# Pendu_LED.net
KiCad netlist of a schematic drawn in EasyEDA
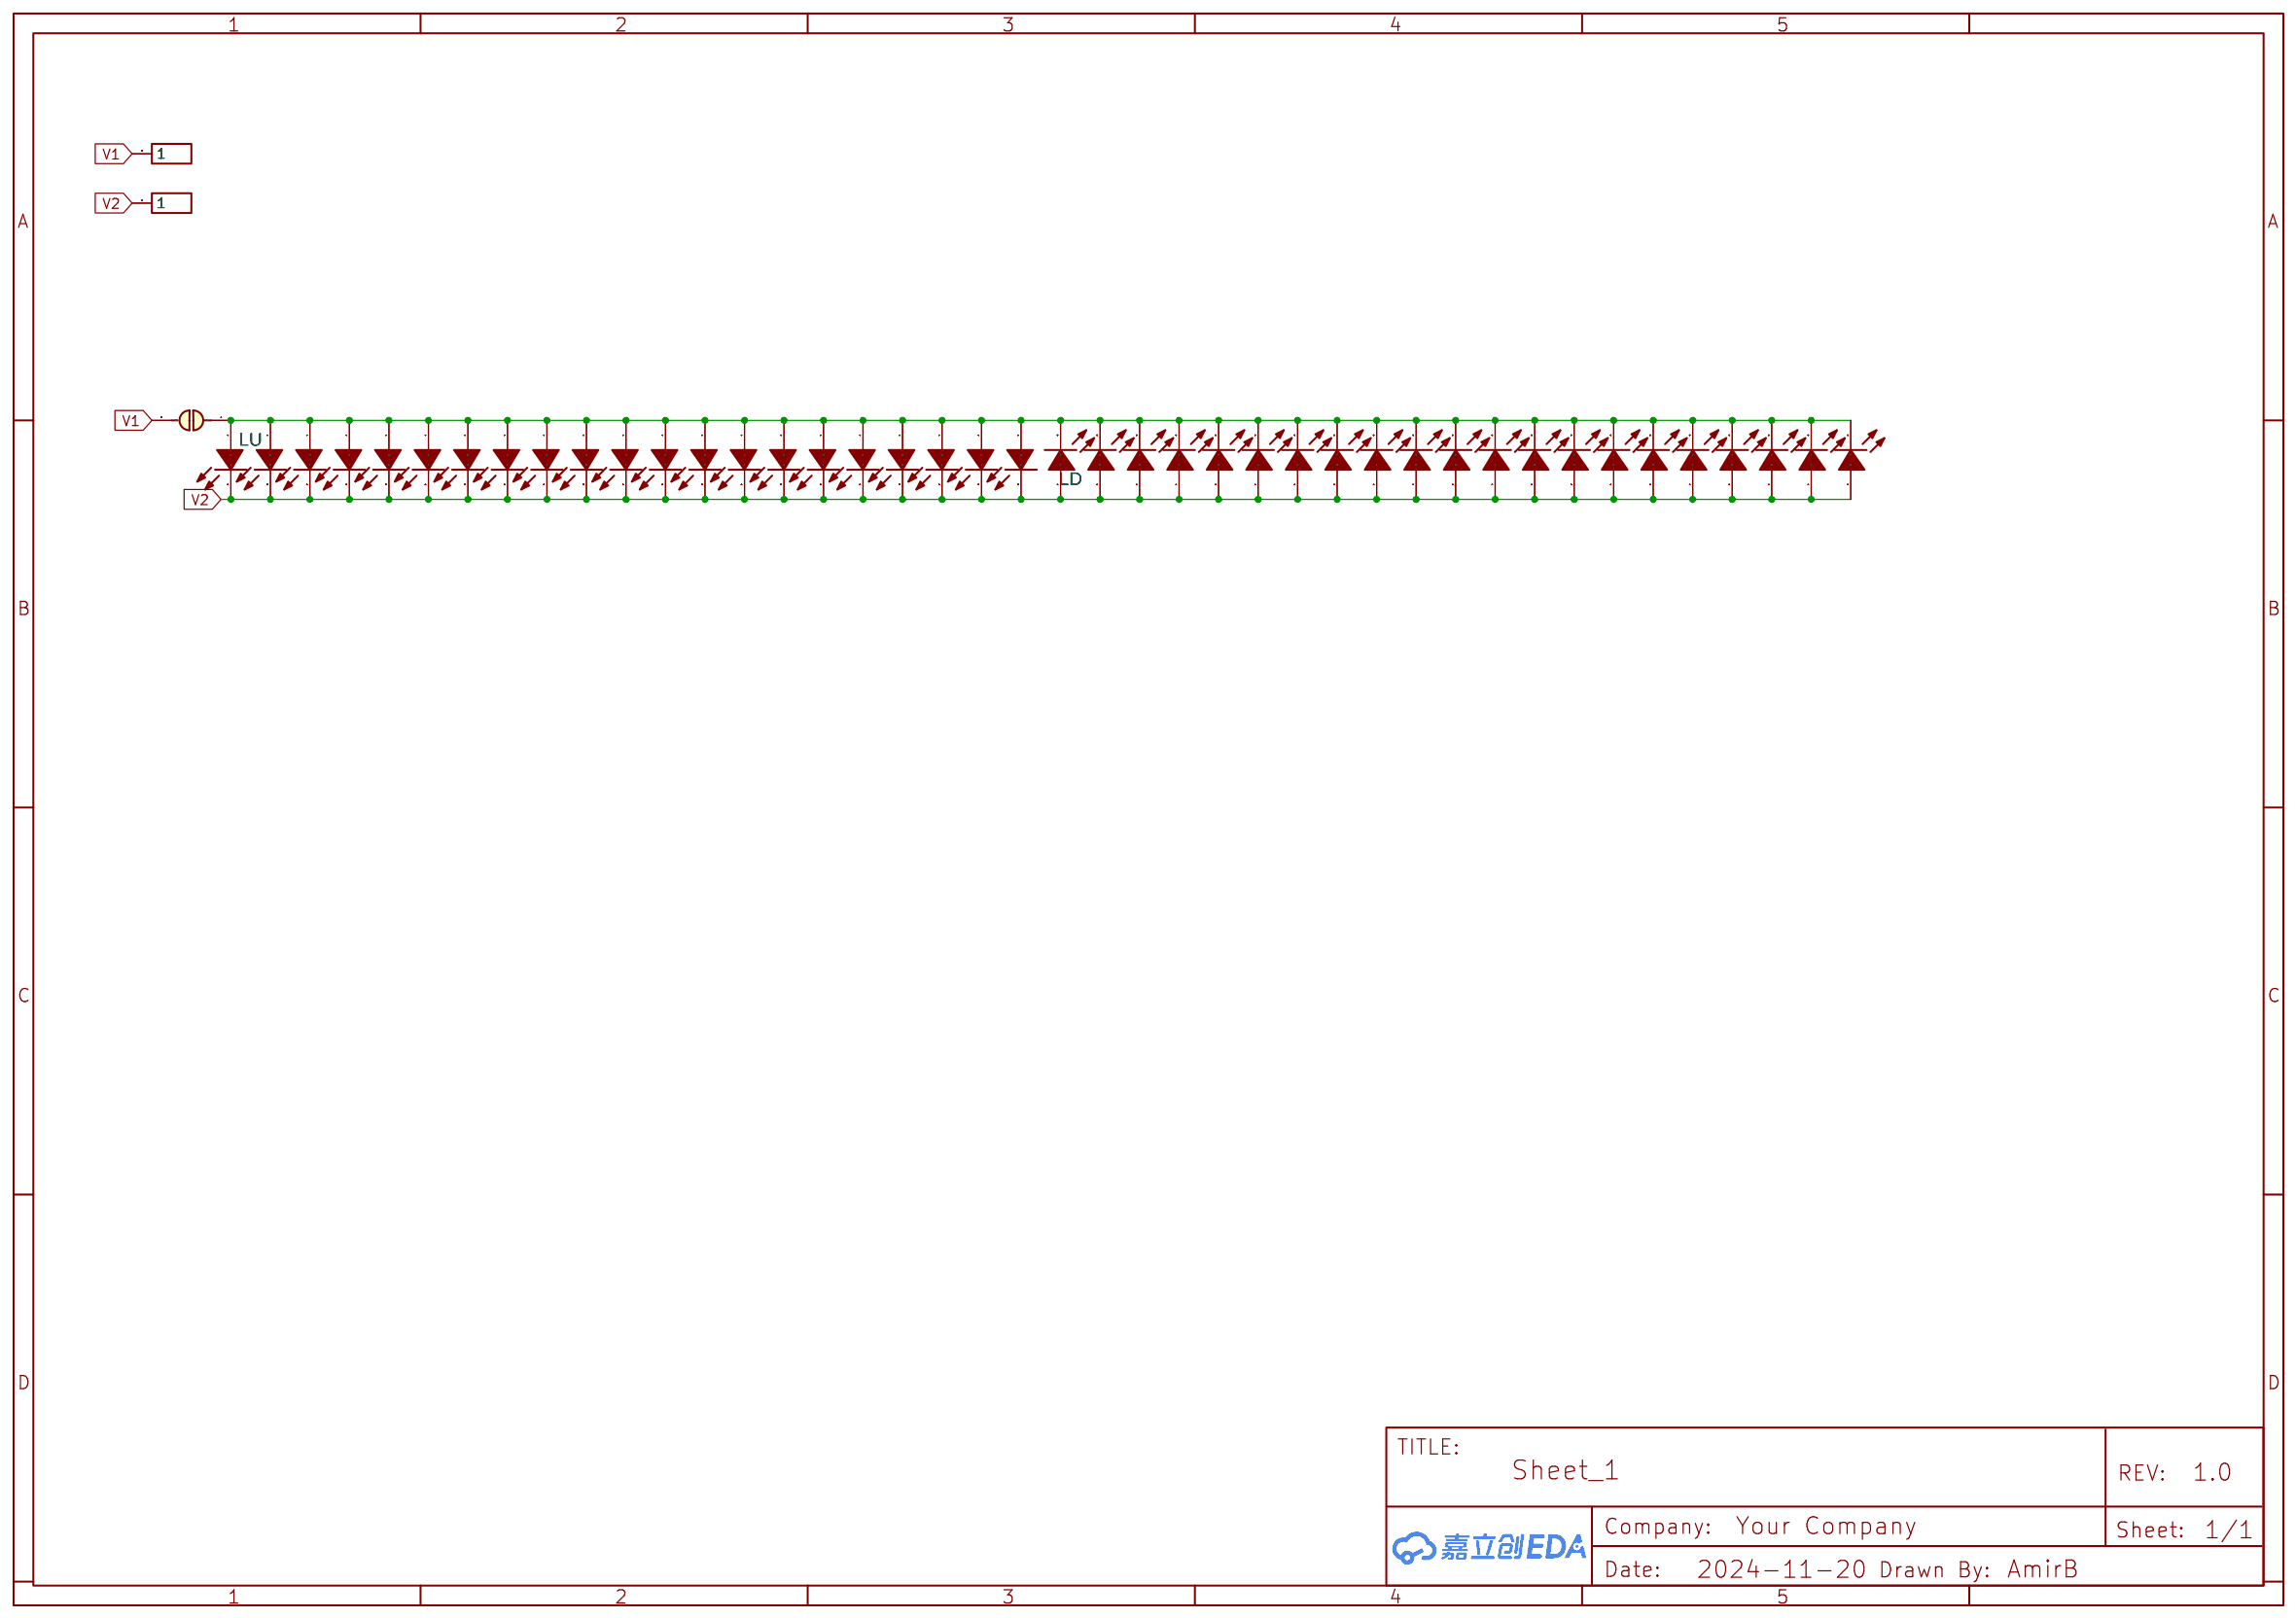
[diagram p0: schematic sheet]

(export (version "E")
  (design (tool "Eeschema 10.0.6"))
  (components
    (comp (ref "J1")
      (value "HDR-M-2.54_1x1")
      (fields (field (name "BOM_Supplier Part") "C81276"))
      (libsource (lib "") (part "HDR-M-2.54_1x1"))
    )
    (comp (ref "J2")
      (value "HDR-M-2.54_1x1")
      (fields (field (name "BOM_Supplier Part") "C81276"))
      (libsource (lib "") (part "HDR-M-2.54_1x1"))
    )
    (comp (ref "JU1") (value "JUMPER-RESET") (libsource (lib "") (part "JUMPER-SMT_2")))
    (comp (ref "LD")
      (value "FC-2012HRK-620D")
      (fields (field (name "Manufacturer Part") "NCD0805R1") (field (name "Manufacturer") "国星光电"))
      (libsource (lib "") (part "FC-2012HRK-620D"))
    )
    (comp (ref "LD1")
      (value "FC-2012HRK-620D")
      (fields (field (name "Manufacturer Part") "NCD0805R1") (field (name "Manufacturer") "国星光电"))
      (libsource (lib "") (part "FC-2012HRK-620D"))
    )
    (comp (ref "LD2")
      (value "FC-2012HRK-620D")
      (fields (field (name "Manufacturer Part") "NCD0805R1") (field (name "Manufacturer") "国星光电"))
      (libsource (lib "") (part "FC-2012HRK-620D"))
    )
    (comp (ref "LD3")
      (value "FC-2012HRK-620D")
      (fields (field (name "Manufacturer Part") "NCD0805R1") (field (name "Manufacturer") "国星光电"))
      (libsource (lib "") (part "FC-2012HRK-620D"))
    )
    (comp (ref "LD4")
      (value "FC-2012HRK-620D")
      (fields (field (name "Manufacturer Part") "NCD0805R1") (field (name "Manufacturer") "国星光电"))
      (libsource (lib "") (part "FC-2012HRK-620D"))
    )
    (comp (ref "LD5")
      (value "FC-2012HRK-620D")
      (fields (field (name "Manufacturer Part") "NCD0805R1") (field (name "Manufacturer") "国星光电"))
      (libsource (lib "") (part "FC-2012HRK-620D"))
    )
    (comp (ref "LD6")
      (value "FC-2012HRK-620D")
      (fields (field (name "Manufacturer Part") "NCD0805R1") (field (name "Manufacturer") "国星光电"))
      (libsource (lib "") (part "FC-2012HRK-620D"))
    )
    (comp (ref "LD7")
      (value "FC-2012HRK-620D")
      (fields (field (name "Manufacturer Part") "NCD0805R1") (field (name "Manufacturer") "国星光电"))
      (libsource (lib "") (part "FC-2012HRK-620D"))
    )
    (comp (ref "LD8")
      (value "FC-2012HRK-620D")
      (fields (field (name "Manufacturer Part") "NCD0805R1") (field (name "Manufacturer") "国星光电"))
      (libsource (lib "") (part "FC-2012HRK-620D"))
    )
    (comp (ref "LD9")
      (value "FC-2012HRK-620D")
      (fields (field (name "Manufacturer Part") "NCD0805R1") (field (name "Manufacturer") "国星光电"))
      (libsource (lib "") (part "FC-2012HRK-620D"))
    )
    (comp (ref "LD10")
      (value "FC-2012HRK-620D")
      (fields (field (name "Manufacturer Part") "NCD0805R1") (field (name "Manufacturer") "国星光电"))
      (libsource (lib "") (part "FC-2012HRK-620D"))
    )
    (comp (ref "LD11")
      (value "FC-2012HRK-620D")
      (fields (field (name "Manufacturer Part") "NCD0805R1") (field (name "Manufacturer") "国星光电"))
      (libsource (lib "") (part "FC-2012HRK-620D"))
    )
    (comp (ref "LD12")
      (value "FC-2012HRK-620D")
      (fields (field (name "Manufacturer Part") "NCD0805R1") (field (name "Manufacturer") "国星光电"))
      (libsource (lib "") (part "FC-2012HRK-620D"))
    )
    (comp (ref "LD13")
      (value "FC-2012HRK-620D")
      (fields (field (name "Manufacturer Part") "NCD0805R1") (field (name "Manufacturer") "国星光电"))
      (libsource (lib "") (part "FC-2012HRK-620D"))
    )
    (comp (ref "LD14")
      (value "FC-2012HRK-620D")
      (fields (field (name "Manufacturer Part") "NCD0805R1") (field (name "Manufacturer") "国星光电"))
      (libsource (lib "") (part "FC-2012HRK-620D"))
    )
    (comp (ref "LD15")
      (value "FC-2012HRK-620D")
      (fields (field (name "Manufacturer Part") "NCD0805R1") (field (name "Manufacturer") "国星光电"))
      (libsource (lib "") (part "FC-2012HRK-620D"))
    )
    (comp (ref "LD16")
      (value "FC-2012HRK-620D")
      (fields (field (name "Manufacturer Part") "NCD0805R1") (field (name "Manufacturer") "国星光电"))
      (libsource (lib "") (part "FC-2012HRK-620D"))
    )
    (comp (ref "LD17")
      (value "FC-2012HRK-620D")
      (fields (field (name "Manufacturer Part") "NCD0805R1") (field (name "Manufacturer") "国星光电"))
      (libsource (lib "") (part "FC-2012HRK-620D"))
    )
    (comp (ref "LD18")
      (value "FC-2012HRK-620D")
      (fields (field (name "Manufacturer Part") "NCD0805R1") (field (name "Manufacturer") "国星光电"))
      (libsource (lib "") (part "FC-2012HRK-620D"))
    )
    (comp (ref "LD19")
      (value "FC-2012HRK-620D")
      (fields (field (name "Manufacturer Part") "NCD0805R1") (field (name "Manufacturer") "国星光电"))
      (libsource (lib "") (part "FC-2012HRK-620D"))
    )
    (comp (ref "LD20")
      (value "FC-2012HRK-620D")
      (fields (field (name "Manufacturer Part") "NCD0805R1") (field (name "Manufacturer") "国星光电"))
      (libsource (lib "") (part "FC-2012HRK-620D"))
    )
    (comp (ref "LU")
      (value "FC-2012HRK-620D")
      (fields (field (name "Manufacturer Part") "NCD0805R1") (field (name "Manufacturer") "国星光电"))
      (libsource (lib "") (part "FC-2012HRK-620D_1"))
    )
    (comp (ref "LU1")
      (value "FC-2012HRK-620D")
      (fields (field (name "Manufacturer Part") "NCD0805R1") (field (name "Manufacturer") "国星光电"))
      (libsource (lib "") (part "FC-2012HRK-620D_1"))
    )
    (comp (ref "LU2")
      (value "FC-2012HRK-620D")
      (fields (field (name "Manufacturer Part") "NCD0805R1") (field (name "Manufacturer") "国星光电"))
      (libsource (lib "") (part "FC-2012HRK-620D_1"))
    )
    (comp (ref "LU3")
      (value "FC-2012HRK-620D")
      (fields (field (name "Manufacturer Part") "NCD0805R1") (field (name "Manufacturer") "国星光电"))
      (libsource (lib "") (part "FC-2012HRK-620D_1"))
    )
    (comp (ref "LU4")
      (value "FC-2012HRK-620D")
      (fields (field (name "Manufacturer Part") "NCD0805R1") (field (name "Manufacturer") "国星光电"))
      (libsource (lib "") (part "FC-2012HRK-620D_1"))
    )
    (comp (ref "LU5")
      (value "FC-2012HRK-620D")
      (fields (field (name "Manufacturer Part") "NCD0805R1") (field (name "Manufacturer") "国星光电"))
      (libsource (lib "") (part "FC-2012HRK-620D_1"))
    )
    (comp (ref "LU6")
      (value "FC-2012HRK-620D")
      (fields (field (name "Manufacturer Part") "NCD0805R1") (field (name "Manufacturer") "国星光电"))
      (libsource (lib "") (part "FC-2012HRK-620D_1"))
    )
    (comp (ref "LU7")
      (value "FC-2012HRK-620D")
      (fields (field (name "Manufacturer Part") "NCD0805R1") (field (name "Manufacturer") "国星光电"))
      (libsource (lib "") (part "FC-2012HRK-620D_1"))
    )
    (comp (ref "LU8")
      (value "FC-2012HRK-620D")
      (fields (field (name "Manufacturer Part") "NCD0805R1") (field (name "Manufacturer") "国星光电"))
      (libsource (lib "") (part "FC-2012HRK-620D_1"))
    )
    (comp (ref "LU9")
      (value "FC-2012HRK-620D")
      (fields (field (name "Manufacturer Part") "NCD0805R1") (field (name "Manufacturer") "国星光电"))
      (libsource (lib "") (part "FC-2012HRK-620D_1"))
    )
    (comp (ref "LU10")
      (value "FC-2012HRK-620D")
      (fields (field (name "Manufacturer Part") "NCD0805R1") (field (name "Manufacturer") "国星光电"))
      (libsource (lib "") (part "FC-2012HRK-620D_1"))
    )
    (comp (ref "LU11")
      (value "FC-2012HRK-620D")
      (fields (field (name "Manufacturer Part") "NCD0805R1") (field (name "Manufacturer") "国星光电"))
      (libsource (lib "") (part "FC-2012HRK-620D_1"))
    )
    (comp (ref "LU12")
      (value "FC-2012HRK-620D")
      (fields (field (name "Manufacturer Part") "NCD0805R1") (field (name "Manufacturer") "国星光电"))
      (libsource (lib "") (part "FC-2012HRK-620D_1"))
    )
    (comp (ref "LU13")
      (value "FC-2012HRK-620D")
      (fields (field (name "Manufacturer Part") "NCD0805R1") (field (name "Manufacturer") "国星光电"))
      (libsource (lib "") (part "FC-2012HRK-620D_1"))
    )
    (comp (ref "LU14")
      (value "FC-2012HRK-620D")
      (fields (field (name "Manufacturer Part") "NCD0805R1") (field (name "Manufacturer") "国星光电"))
      (libsource (lib "") (part "FC-2012HRK-620D_1"))
    )
    (comp (ref "LU15")
      (value "FC-2012HRK-620D")
      (fields (field (name "Manufacturer Part") "NCD0805R1") (field (name "Manufacturer") "国星光电"))
      (libsource (lib "") (part "FC-2012HRK-620D_1"))
    )
    (comp (ref "LU16")
      (value "FC-2012HRK-620D")
      (fields (field (name "Manufacturer Part") "NCD0805R1") (field (name "Manufacturer") "国星光电"))
      (libsource (lib "") (part "FC-2012HRK-620D_1"))
    )
    (comp (ref "LU17")
      (value "FC-2012HRK-620D")
      (fields (field (name "Manufacturer Part") "NCD0805R1") (field (name "Manufacturer") "国星光电"))
      (libsource (lib "") (part "FC-2012HRK-620D_1"))
    )
    (comp (ref "LU18")
      (value "FC-2012HRK-620D")
      (fields (field (name "Manufacturer Part") "NCD0805R1") (field (name "Manufacturer") "国星光电"))
      (libsource (lib "") (part "FC-2012HRK-620D_1"))
    )
    (comp (ref "LU19")
      (value "FC-2012HRK-620D")
      (fields (field (name "Manufacturer Part") "NCD0805R1") (field (name "Manufacturer") "国星光电"))
      (libsource (lib "") (part "FC-2012HRK-620D_1"))
    )
    (comp (ref "LU20")
      (value "FC-2012HRK-620D")
      (fields (field (name "Manufacturer Part") "NCD0805R1") (field (name "Manufacturer") "国星光电"))
      (libsource (lib "") (part "FC-2012HRK-620D_1"))
    )
  )
  (nets
    (net (code "1") (name "Net-(LD--)") (class "Default")
      (node (ref "JU1") (pin "1") (pinfunction "1_1") (pintype "bidirectional"))
      (node (ref "LD") (pin "2") (pinfunction "-_2") (pintype "unspecified"))
      (node (ref "LD1") (pin "2") (pinfunction "-_2") (pintype "unspecified"))
      (node (ref "LD10") (pin "2") (pinfunction "-_2") (pintype "unspecified"))
      (node (ref "LD11") (pin "2") (pinfunction "-_2") (pintype "unspecified"))
      (node (ref "LD12") (pin "2") (pinfunction "-_2") (pintype "unspecified"))
      (node (ref "LD13") (pin "2") (pinfunction "-_2") (pintype "unspecified"))
      (node (ref "LD14") (pin "2") (pinfunction "-_2") (pintype "unspecified"))
      (node (ref "LD15") (pin "2") (pinfunction "-_2") (pintype "unspecified"))
      (node (ref "LD16") (pin "2") (pinfunction "-_2") (pintype "unspecified"))
      (node (ref "LD17") (pin "2") (pinfunction "-_2") (pintype "unspecified"))
      (node (ref "LD18") (pin "2") (pinfunction "-_2") (pintype "unspecified"))
      (node (ref "LD19") (pin "2") (pinfunction "-_2") (pintype "unspecified"))
      (node (ref "LD2") (pin "2") (pinfunction "-_2") (pintype "unspecified"))
      (node (ref "LD20") (pin "2") (pinfunction "-_2") (pintype "unspecified"))
      (node (ref "LD3") (pin "2") (pinfunction "-_2") (pintype "unspecified"))
      (node (ref "LD4") (pin "2") (pinfunction "-_2") (pintype "unspecified"))
      (node (ref "LD5") (pin "2") (pinfunction "-_2") (pintype "unspecified"))
      (node (ref "LD6") (pin "2") (pinfunction "-_2") (pintype "unspecified"))
      (node (ref "LD7") (pin "2") (pinfunction "-_2") (pintype "unspecified"))
      (node (ref "LD8") (pin "2") (pinfunction "-_2") (pintype "unspecified"))
      (node (ref "LD9") (pin "2") (pinfunction "-_2") (pintype "unspecified"))
      (node (ref "LU") (pin "1") (pinfunction "+_1") (pintype "unspecified"))
      (node (ref "LU1") (pin "1") (pinfunction "+_1") (pintype "unspecified"))
      (node (ref "LU10") (pin "1") (pinfunction "+_1") (pintype "unspecified"))
      (node (ref "LU11") (pin "1") (pinfunction "+_1") (pintype "unspecified"))
      (node (ref "LU12") (pin "1") (pinfunction "+_1") (pintype "unspecified"))
      (node (ref "LU13") (pin "1") (pinfunction "+_1") (pintype "unspecified"))
      (node (ref "LU14") (pin "1") (pinfunction "+_1") (pintype "unspecified"))
      (node (ref "LU15") (pin "1") (pinfunction "+_1") (pintype "unspecified"))
      (node (ref "LU16") (pin "1") (pinfunction "+_1") (pintype "unspecified"))
      (node (ref "LU17") (pin "1") (pinfunction "+_1") (pintype "unspecified"))
      (node (ref "LU18") (pin "1") (pinfunction "+_1") (pintype "unspecified"))
      (node (ref "LU19") (pin "1") (pinfunction "+_1") (pintype "unspecified"))
      (node (ref "LU2") (pin "1") (pinfunction "+_1") (pintype "unspecified"))
      (node (ref "LU20") (pin "1") (pinfunction "+_1") (pintype "unspecified"))
      (node (ref "LU3") (pin "1") (pinfunction "+_1") (pintype "unspecified"))
      (node (ref "LU4") (pin "1") (pinfunction "+_1") (pintype "unspecified"))
      (node (ref "LU5") (pin "1") (pinfunction "+_1") (pintype "unspecified"))
      (node (ref "LU6") (pin "1") (pinfunction "+_1") (pintype "unspecified"))
      (node (ref "LU7") (pin "1") (pinfunction "+_1") (pintype "unspecified"))
      (node (ref "LU8") (pin "1") (pinfunction "+_1") (pintype "unspecified"))
      (node (ref "LU9") (pin "1") (pinfunction "+_1") (pintype "unspecified"))
    )
    (net (code "2") (name "V1") (class "Default")
      (node (ref "J1") (pin "1") (pinfunction "1_1") (pintype "input"))
      (node (ref "JU1") (pin "2") (pinfunction "2_2") (pintype "bidirectional"))
    )
    (net (code "3") (name "V2") (class "Default")
      (node (ref "J2") (pin "1") (pinfunction "1_1") (pintype "input"))
      (node (ref "LD") (pin "1") (pinfunction "+_1") (pintype "unspecified"))
      (node (ref "LD1") (pin "1") (pinfunction "+_1") (pintype "unspecified"))
      (node (ref "LD10") (pin "1") (pinfunction "+_1") (pintype "unspecified"))
      (node (ref "LD11") (pin "1") (pinfunction "+_1") (pintype "unspecified"))
      (node (ref "LD12") (pin "1") (pinfunction "+_1") (pintype "unspecified"))
      (node (ref "LD13") (pin "1") (pinfunction "+_1") (pintype "unspecified"))
      (node (ref "LD14") (pin "1") (pinfunction "+_1") (pintype "unspecified"))
      (node (ref "LD15") (pin "1") (pinfunction "+_1") (pintype "unspecified"))
      (node (ref "LD16") (pin "1") (pinfunction "+_1") (pintype "unspecified"))
      (node (ref "LD17") (pin "1") (pinfunction "+_1") (pintype "unspecified"))
      (node (ref "LD18") (pin "1") (pinfunction "+_1") (pintype "unspecified"))
      (node (ref "LD19") (pin "1") (pinfunction "+_1") (pintype "unspecified"))
      (node (ref "LD2") (pin "1") (pinfunction "+_1") (pintype "unspecified"))
      (node (ref "LD20") (pin "1") (pinfunction "+_1") (pintype "unspecified"))
      (node (ref "LD3") (pin "1") (pinfunction "+_1") (pintype "unspecified"))
      (node (ref "LD4") (pin "1") (pinfunction "+_1") (pintype "unspecified"))
      (node (ref "LD5") (pin "1") (pinfunction "+_1") (pintype "unspecified"))
      (node (ref "LD6") (pin "1") (pinfunction "+_1") (pintype "unspecified"))
      (node (ref "LD7") (pin "1") (pinfunction "+_1") (pintype "unspecified"))
      (node (ref "LD8") (pin "1") (pinfunction "+_1") (pintype "unspecified"))
      (node (ref "LD9") (pin "1") (pinfunction "+_1") (pintype "unspecified"))
      (node (ref "LU") (pin "2") (pinfunction "-_2") (pintype "unspecified"))
      (node (ref "LU1") (pin "2") (pinfunction "-_2") (pintype "unspecified"))
      (node (ref "LU10") (pin "2") (pinfunction "-_2") (pintype "unspecified"))
      (node (ref "LU11") (pin "2") (pinfunction "-_2") (pintype "unspecified"))
      (node (ref "LU12") (pin "2") (pinfunction "-_2") (pintype "unspecified"))
      (node (ref "LU13") (pin "2") (pinfunction "-_2") (pintype "unspecified"))
      (node (ref "LU14") (pin "2") (pinfunction "-_2") (pintype "unspecified"))
      (node (ref "LU15") (pin "2") (pinfunction "-_2") (pintype "unspecified"))
      (node (ref "LU16") (pin "2") (pinfunction "-_2") (pintype "unspecified"))
      (node (ref "LU17") (pin "2") (pinfunction "-_2") (pintype "unspecified"))
      (node (ref "LU18") (pin "2") (pinfunction "-_2") (pintype "unspecified"))
      (node (ref "LU19") (pin "2") (pinfunction "-_2") (pintype "unspecified"))
      (node (ref "LU2") (pin "2") (pinfunction "-_2") (pintype "unspecified"))
      (node (ref "LU20") (pin "2") (pinfunction "-_2") (pintype "unspecified"))
      (node (ref "LU3") (pin "2") (pinfunction "-_2") (pintype "unspecified"))
      (node (ref "LU4") (pin "2") (pinfunction "-_2") (pintype "unspecified"))
      (node (ref "LU5") (pin "2") (pinfunction "-_2") (pintype "unspecified"))
      (node (ref "LU6") (pin "2") (pinfunction "-_2") (pintype "unspecified"))
      (node (ref "LU7") (pin "2") (pinfunction "-_2") (pintype "unspecified"))
      (node (ref "LU8") (pin "2") (pinfunction "-_2") (pintype "unspecified"))
      (node (ref "LU9") (pin "2") (pinfunction "-_2") (pintype "unspecified"))
    )
  )
)
